# Canzasi-Cont.net
KiCad netlist of a schematic drawn in EAGLE
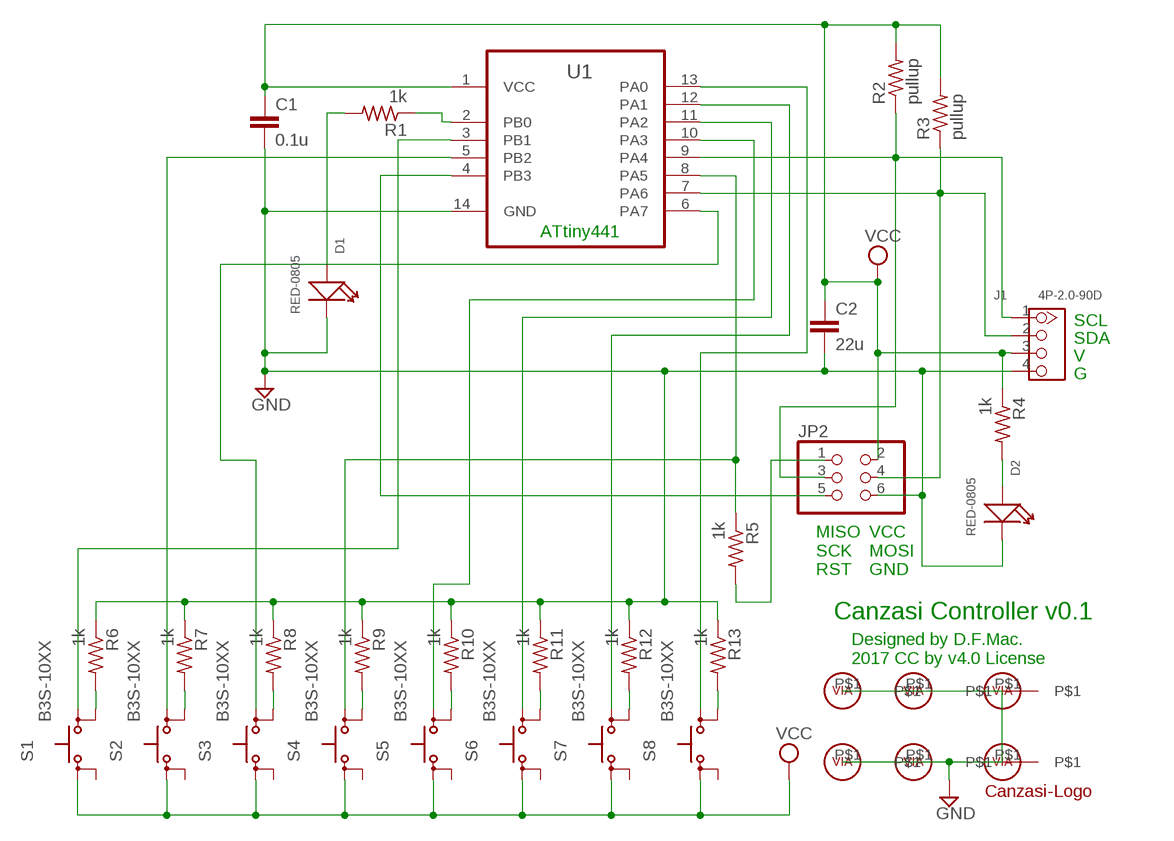
[diagram p0: schematic, sheet 1]

(export (version "E")
  (design (tool "Eeschema 10.0.6"))
  (components
    (comp (ref "C1")
      (value "0.1u")
      (footprint "eagle-import:C0603")
      (libsource (lib "eagle-import") (part "C-EUC0603"))
    )
    (comp (ref "C2")
      (value "22u")
      (footprint "eagle-import:C0805")
      (libsource (lib "eagle-import") (part "C-EUC0805"))
    )
    (comp (ref "D1")
      (value "RED-0805")
      (footprint "eagle-import:LED-0805")
      (fields (field (name "MPN") "17-215SURC/S530-A2/TR8"))
      (libsource (lib "eagle-import") (part "SMD-LED-CLEAR-RED(0805)"))
    )
    (comp (ref "D2")
      (value "RED-0805")
      (footprint "eagle-import:LED-0805")
      (fields (field (name "MPN") "17-215SURC/S530-A2/TR8"))
      (libsource (lib "eagle-import") (part "SMD-LED-CLEAR-RED(0805)"))
    )
    (comp (ref "J1")
      (value "4P-2.0-90D")
      (footprint "eagle-import:HW4-2.0-90D")
      (libsource (lib "eagle-import") (part "GROVE-CONNECTOR-DIP-90D(4P-2.0)"))
    )
    (comp (ref "JP2")
      (value "PINHD-2X3")
      (footprint "eagle-import:2X03")
      (libsource (lib "eagle-import") (part "PINHD-2X3"))
    )
    (comp (ref "R1")
      (value "1k")
      (footprint "eagle-import:R0603")
      (libsource (lib "eagle-import") (part "R-US_R0603"))
    )
    (comp (ref "R2")
      (value "pullup")
      (footprint "eagle-import:R0603")
      (libsource (lib "eagle-import") (part "R-US_R0603"))
    )
    (comp (ref "R3")
      (value "pullup")
      (footprint "eagle-import:R0603")
      (libsource (lib "eagle-import") (part "R-US_R0603"))
    )
    (comp (ref "R4")
      (value "1k")
      (footprint "eagle-import:R0603")
      (libsource (lib "eagle-import") (part "R-US_R0603"))
    )
    (comp (ref "R5")
      (value "1k")
      (footprint "eagle-import:R0603")
      (libsource (lib "eagle-import") (part "R-US_R0603"))
    )
    (comp (ref "R6")
      (value "1k")
      (footprint "eagle-import:R0603")
      (libsource (lib "eagle-import") (part "R-US_R0603"))
    )
    (comp (ref "R7")
      (value "1k")
      (footprint "eagle-import:R0603")
      (libsource (lib "eagle-import") (part "R-US_R0603"))
    )
    (comp (ref "R8")
      (value "1k")
      (footprint "eagle-import:R0603")
      (libsource (lib "eagle-import") (part "R-US_R0603"))
    )
    (comp (ref "R9")
      (value "1k")
      (footprint "eagle-import:R0603")
      (libsource (lib "eagle-import") (part "R-US_R0603"))
    )
    (comp (ref "R10")
      (value "1k")
      (footprint "eagle-import:R0603")
      (libsource (lib "eagle-import") (part "R-US_R0603"))
    )
    (comp (ref "R11")
      (value "1k")
      (footprint "eagle-import:R0603")
      (libsource (lib "eagle-import") (part "R-US_R0603"))
    )
    (comp (ref "R12")
      (value "1k")
      (footprint "eagle-import:R0603")
      (libsource (lib "eagle-import") (part "R-US_R0603"))
    )
    (comp (ref "R13")
      (value "1k")
      (footprint "eagle-import:R0603")
      (libsource (lib "eagle-import") (part "R-US_R0603"))
    )
    (comp (ref "S1")
      (value "B3S-10XX")
      (footprint "eagle-import:B3S-10XX")
      (libsource (lib "eagle-import") (part "B3S-10XX"))
    )
    (comp (ref "S2")
      (value "B3S-10XX")
      (footprint "eagle-import:B3S-10XX")
      (libsource (lib "eagle-import") (part "B3S-10XX"))
    )
    (comp (ref "S3")
      (value "B3S-10XX")
      (footprint "eagle-import:B3S-10XX")
      (libsource (lib "eagle-import") (part "B3S-10XX"))
    )
    (comp (ref "S4")
      (value "B3S-10XX")
      (footprint "eagle-import:B3S-10XX")
      (libsource (lib "eagle-import") (part "B3S-10XX"))
    )
    (comp (ref "S5")
      (value "B3S-10XX")
      (footprint "eagle-import:B3S-10XX")
      (libsource (lib "eagle-import") (part "B3S-10XX"))
    )
    (comp (ref "S6")
      (value "B3S-10XX")
      (footprint "eagle-import:B3S-10XX")
      (libsource (lib "eagle-import") (part "B3S-10XX"))
    )
    (comp (ref "S7")
      (value "B3S-10XX")
      (footprint "eagle-import:B3S-10XX")
      (libsource (lib "eagle-import") (part "B3S-10XX"))
    )
    (comp (ref "S8")
      (value "B3S-10XX")
      (footprint "eagle-import:B3S-10XX")
      (libsource (lib "eagle-import") (part "B3S-10XX"))
    )
    (comp (ref "U$1")
      (value "CANZASI-LOGOMEDIUM")
      (footprint "eagle-import:CANZASI-LOGO-MEDIUM")
      (libsource (lib "eagle-import") (part "CANZASI-LOGOMEDIUM"))
    )
    (comp (ref "U$2")
      (value "VIA")
      (footprint "eagle-import:VIA")
      (libsource (lib "eagle-import") (part "VIA"))
    )
    (comp (ref "U$3")
      (value "VIA")
      (footprint "eagle-import:VIA")
      (libsource (lib "eagle-import") (part "VIA"))
    )
    (comp (ref "U$4")
      (value "VIA")
      (footprint "eagle-import:VIA")
      (libsource (lib "eagle-import") (part "VIA"))
    )
    (comp (ref "U$5")
      (value "VIA")
      (footprint "eagle-import:VIA")
      (libsource (lib "eagle-import") (part "VIA"))
    )
    (comp (ref "U$6")
      (value "VIA")
      (footprint "eagle-import:VIA")
      (libsource (lib "eagle-import") (part "VIA"))
    )
    (comp (ref "U$7")
      (value "VIA")
      (footprint "eagle-import:VIA")
      (libsource (lib "eagle-import") (part "VIA"))
    )
    (comp (ref "U1")
      (value "ATTINY44A-SSU")
      (footprint "eagle-import:SOIC127P600X175-14N")
      (libsource (lib "eagle-import") (part "ATTINY44A-SSU"))
    )
  )
  (nets
    (net (code "1") (name "GND") (class "Default")
      (node (ref "C1") (pin "2") (pinfunction "2_2") (pintype "passive"))
      (node (ref "C2") (pin "2") (pinfunction "2_2") (pintype "passive"))
      (node (ref "D1") (pin "-") (pinfunction "-_-") (pintype "passive"))
      (node (ref "D2") (pin "-") (pinfunction "-_-") (pintype "passive"))
      (node (ref "J1") (pin "4") (pinfunction "4_4") (pintype "bidirectional"))
      (node (ref "JP2") (pin "6") (pinfunction "6_6") (pintype "passive"))
      (node (ref "R10") (pin "1") (pinfunction "1_1") (pintype "passive"))
      (node (ref "R11") (pin "1") (pinfunction "1_1") (pintype "passive"))
      (node (ref "R12") (pin "1") (pinfunction "1_1") (pintype "passive"))
      (node (ref "R13") (pin "1") (pinfunction "1_1") (pintype "passive"))
      (node (ref "R6") (pin "1") (pinfunction "1_1") (pintype "passive"))
      (node (ref "R7") (pin "1") (pinfunction "1_1") (pintype "passive"))
      (node (ref "R8") (pin "1") (pinfunction "1_1") (pintype "passive"))
      (node (ref "R9") (pin "1") (pinfunction "1_1") (pintype "passive"))
      (node (ref "U$2") (pin "P$1") (pinfunction "P$1_P$1") (pintype "bidirectional"))
      (node (ref "U$3") (pin "P$1") (pinfunction "P$1_P$1") (pintype "bidirectional"))
      (node (ref "U$4") (pin "P$1") (pinfunction "P$1_P$1") (pintype "bidirectional"))
      (node (ref "U$5") (pin "P$1") (pinfunction "P$1_P$1") (pintype "bidirectional"))
      (node (ref "U$6") (pin "P$1") (pinfunction "P$1_P$1") (pintype "bidirectional"))
      (node (ref "U$7") (pin "P$1") (pinfunction "P$1_P$1") (pintype "bidirectional"))
      (node (ref "U1") (pin "14") (pinfunction "GND_14") (pintype "power_in"))
    )
    (net (code "2") (name "Net-(D1-Pad+)") (class "Default")
      (node (ref "D1") (pin "+") (pinfunction "+_+") (pintype "passive"))
      (node (ref "R1") (pin "2") (pinfunction "2_2") (pintype "passive"))
    )
    (net (code "3") (name "Net-(D2-Pad+)") (class "Default")
      (node (ref "D2") (pin "+") (pinfunction "+_+") (pintype "passive"))
      (node (ref "R4") (pin "2") (pinfunction "2_2") (pintype "passive"))
    )
    (net (code "4") (name "Net-(JP2-Pad1)") (class "Default")
      (node (ref "JP2") (pin "1") (pinfunction "1_1") (pintype "passive"))
      (node (ref "R5") (pin "2") (pinfunction "2_2") (pintype "passive"))
    )
    (net (code "5") (name "Net-(S1-S)") (class "Default")
      (node (ref "S1") (pin "3") (pinfunction "S_3") (pintype "passive"))
      (node (ref "U1") (pin "3") (pinfunction "PB1_3") (pintype "bidirectional"))
    )
    (net (code "6") (name "Net-(S1-S1)") (class "Default")
      (node (ref "R6") (pin "2") (pinfunction "2_2") (pintype "passive"))
      (node (ref "S1") (pin "4") (pinfunction "S1_4") (pintype "passive"))
    )
    (net (code "7") (name "Net-(S2-S)") (class "Default")
      (node (ref "S2") (pin "3") (pinfunction "S_3") (pintype "passive"))
      (node (ref "U1") (pin "5") (pinfunction "PB2_5") (pintype "bidirectional"))
    )
    (net (code "8") (name "Net-(S2-S1)") (class "Default")
      (node (ref "R7") (pin "2") (pinfunction "2_2") (pintype "passive"))
      (node (ref "S2") (pin "4") (pinfunction "S1_4") (pintype "passive"))
    )
    (net (code "9") (name "Net-(S3-S)") (class "Default")
      (node (ref "S3") (pin "3") (pinfunction "S_3") (pintype "passive"))
      (node (ref "U1") (pin "6") (pinfunction "PA7_6") (pintype "bidirectional"))
    )
    (net (code "10") (name "Net-(S3-S1)") (class "Default")
      (node (ref "R8") (pin "2") (pinfunction "2_2") (pintype "passive"))
      (node (ref "S3") (pin "4") (pinfunction "S1_4") (pintype "passive"))
    )
    (net (code "11") (name "Net-(S4-S)") (class "Default")
      (node (ref "R5") (pin "1") (pinfunction "1_1") (pintype "passive"))
      (node (ref "S4") (pin "3") (pinfunction "S_3") (pintype "passive"))
      (node (ref "U1") (pin "8") (pinfunction "PA5_8") (pintype "bidirectional"))
    )
    (net (code "12") (name "Net-(S4-S1)") (class "Default")
      (node (ref "R9") (pin "2") (pinfunction "2_2") (pintype "passive"))
      (node (ref "S4") (pin "4") (pinfunction "S1_4") (pintype "passive"))
    )
    (net (code "13") (name "Net-(S5-S)") (class "Default")
      (node (ref "S5") (pin "3") (pinfunction "S_3") (pintype "passive"))
      (node (ref "U1") (pin "10") (pinfunction "PA3_10") (pintype "bidirectional"))
    )
    (net (code "14") (name "Net-(S5-S1)") (class "Default")
      (node (ref "R10") (pin "2") (pinfunction "2_2") (pintype "passive"))
      (node (ref "S5") (pin "4") (pinfunction "S1_4") (pintype "passive"))
    )
    (net (code "15") (name "Net-(S6-S)") (class "Default")
      (node (ref "S6") (pin "3") (pinfunction "S_3") (pintype "passive"))
      (node (ref "U1") (pin "11") (pinfunction "PA2_11") (pintype "bidirectional"))
    )
    (net (code "16") (name "Net-(S6-S1)") (class "Default")
      (node (ref "R11") (pin "2") (pinfunction "2_2") (pintype "passive"))
      (node (ref "S6") (pin "4") (pinfunction "S1_4") (pintype "passive"))
    )
    (net (code "17") (name "Net-(S7-S)") (class "Default")
      (node (ref "S7") (pin "3") (pinfunction "S_3") (pintype "passive"))
      (node (ref "U1") (pin "12") (pinfunction "PA1_12") (pintype "bidirectional"))
    )
    (net (code "18") (name "Net-(S7-S1)") (class "Default")
      (node (ref "R12") (pin "2") (pinfunction "2_2") (pintype "passive"))
      (node (ref "S7") (pin "4") (pinfunction "S1_4") (pintype "passive"))
    )
    (net (code "19") (name "Net-(S8-S)") (class "Default")
      (node (ref "S8") (pin "3") (pinfunction "S_3") (pintype "passive"))
      (node (ref "U1") (pin "13") (pinfunction "PA0_13") (pintype "bidirectional"))
    )
    (net (code "20") (name "Net-(S8-S1)") (class "Default")
      (node (ref "R13") (pin "2") (pinfunction "2_2") (pintype "passive"))
      (node (ref "S8") (pin "4") (pinfunction "S1_4") (pintype "passive"))
    )
    (net (code "21") (name "Net-(U1-PA4)") (class "Default")
      (node (ref "J1") (pin "1") (pinfunction "1_1") (pintype "bidirectional"))
      (node (ref "JP2") (pin "3") (pinfunction "3_3") (pintype "passive"))
      (node (ref "R2") (pin "1") (pinfunction "1_1") (pintype "passive"))
      (node (ref "U1") (pin "9") (pinfunction "PA4_9") (pintype "bidirectional"))
    )
    (net (code "22") (name "Net-(U1-PA6)") (class "Default")
      (node (ref "J1") (pin "2") (pinfunction "2_2") (pintype "bidirectional"))
      (node (ref "JP2") (pin "4") (pinfunction "4_4") (pintype "passive"))
      (node (ref "R3") (pin "1") (pinfunction "1_1") (pintype "passive"))
      (node (ref "U1") (pin "7") (pinfunction "PA6_7") (pintype "bidirectional"))
    )
    (net (code "23") (name "Net-(U1-PB0)") (class "Default")
      (node (ref "R1") (pin "1") (pinfunction "1_1") (pintype "passive"))
      (node (ref "U1") (pin "2") (pinfunction "PB0_2") (pintype "bidirectional"))
    )
    (net (code "24") (name "Net-(U1-PB3)") (class "Default")
      (node (ref "JP2") (pin "5") (pinfunction "5_5") (pintype "passive"))
      (node (ref "U1") (pin "4") (pinfunction "PB3_4") (pintype "bidirectional"))
    )
    (net (code "25") (name "VCC") (class "Default")
      (node (ref "C1") (pin "1") (pinfunction "1_1") (pintype "passive"))
      (node (ref "C2") (pin "1") (pinfunction "1_1") (pintype "passive"))
      (node (ref "J1") (pin "3") (pinfunction "3_3") (pintype "bidirectional"))
      (node (ref "JP2") (pin "2") (pinfunction "2_2") (pintype "passive"))
      (node (ref "R2") (pin "2") (pinfunction "2_2") (pintype "passive"))
      (node (ref "R3") (pin "2") (pinfunction "2_2") (pintype "passive"))
      (node (ref "R4") (pin "1") (pinfunction "1_1") (pintype "passive"))
      (node (ref "S1") (pin "1") (pinfunction "P_1") (pintype "passive"))
      (node (ref "S2") (pin "1") (pinfunction "P_1") (pintype "passive"))
      (node (ref "S3") (pin "1") (pinfunction "P_1") (pintype "passive"))
      (node (ref "S4") (pin "1") (pinfunction "P_1") (pintype "passive"))
      (node (ref "S5") (pin "1") (pinfunction "P_1") (pintype "passive"))
      (node (ref "S6") (pin "1") (pinfunction "P_1") (pintype "passive"))
      (node (ref "S7") (pin "1") (pinfunction "P_1") (pintype "passive"))
      (node (ref "S8") (pin "1") (pinfunction "P_1") (pintype "passive"))
      (node (ref "U1") (pin "1") (pinfunction "VCC_1") (pintype "power_in"))
    )
    (net (code "26") (name "unconnected-(S1-P1-Pad2)") (class "Default")
      (node (ref "S1") (pin "2") (pinfunction "P1_2") (pintype "passive"))
    )
    (net (code "27") (name "unconnected-(S2-P1-Pad2)") (class "Default")
      (node (ref "S2") (pin "2") (pinfunction "P1_2") (pintype "passive"))
    )
    (net (code "28") (name "unconnected-(S3-P1-Pad2)") (class "Default")
      (node (ref "S3") (pin "2") (pinfunction "P1_2") (pintype "passive"))
    )
    (net (code "29") (name "unconnected-(S4-P1-Pad2)") (class "Default")
      (node (ref "S4") (pin "2") (pinfunction "P1_2") (pintype "passive"))
    )
    (net (code "30") (name "unconnected-(S5-P1-Pad2)") (class "Default")
      (node (ref "S5") (pin "2") (pinfunction "P1_2") (pintype "passive"))
    )
    (net (code "31") (name "unconnected-(S6-P1-Pad2)") (class "Default")
      (node (ref "S6") (pin "2") (pinfunction "P1_2") (pintype "passive"))
    )
    (net (code "32") (name "unconnected-(S7-P1-Pad2)") (class "Default")
      (node (ref "S7") (pin "2") (pinfunction "P1_2") (pintype "passive"))
    )
    (net (code "33") (name "unconnected-(S8-P1-Pad2)") (class "Default")
      (node (ref "S8") (pin "2") (pinfunction "P1_2") (pintype "passive"))
    )
  )
)
